# NRF51822.net
KiCad netlist of a schematic drawn in Altium Designer
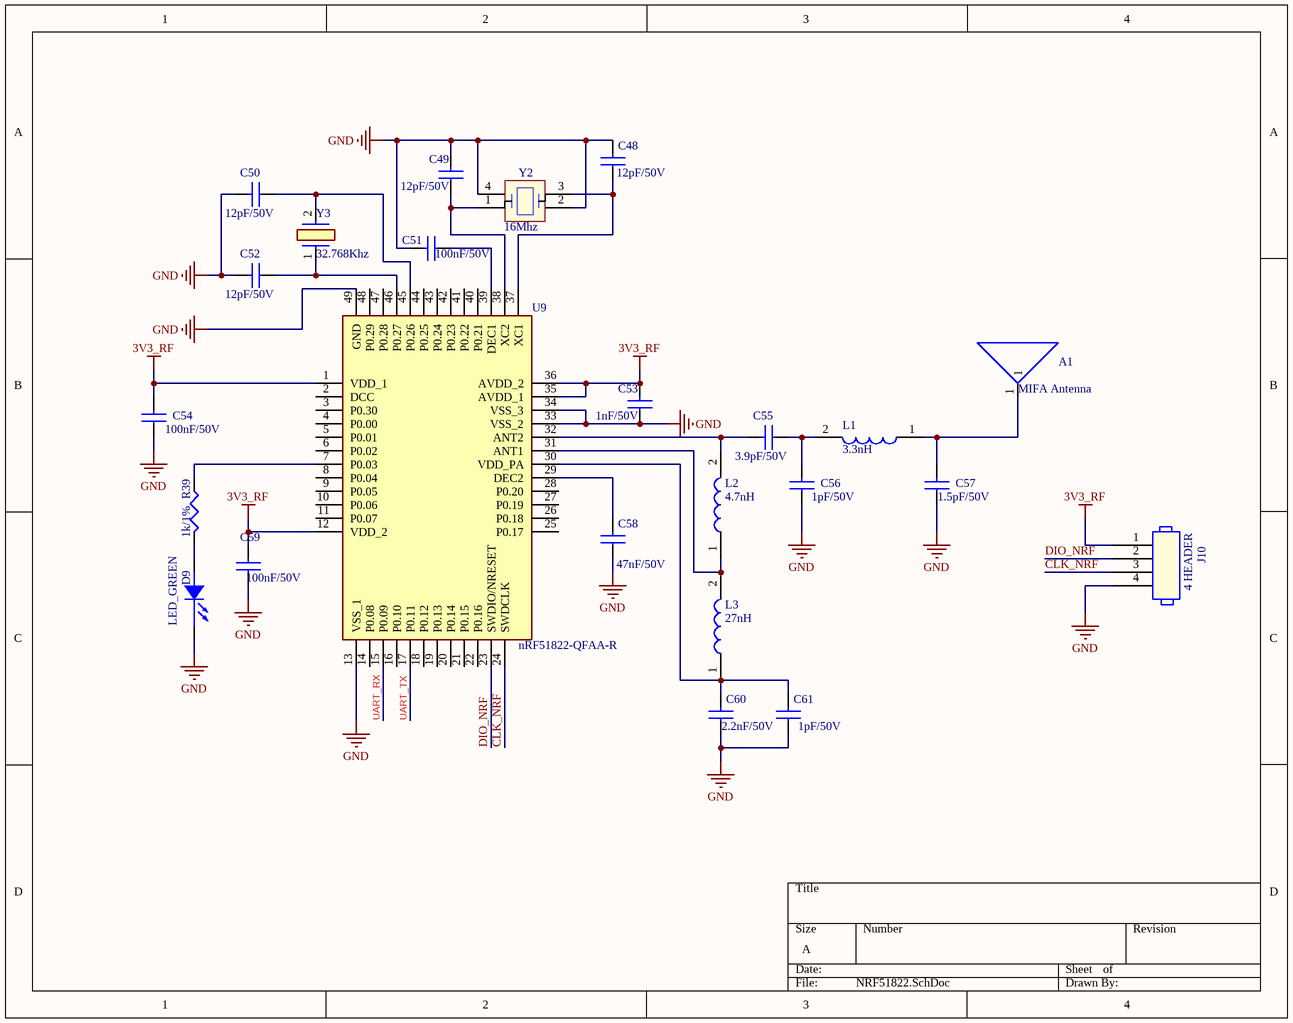
[diagram p0: NRF51822.SchDoc]

(export (version "E")
  (design (tool "Eeschema 10.0.6"))
  (components
    (comp (ref "A1")
      (value "MIFA Antenna")
      (footprint "ANT-2.4GHZ-8.0X1.0MM")
      (description "None")
      (libsource (lib "VESC_DEVICE_Library") (part "Ceramic _ANTENNA"))
    )
    (comp (ref "C48") (value "12pF/50V") (footprint "C0402") (libsource (lib "*") (part "CAP NP")))
    (comp (ref "C49") (value "12pF/50V") (footprint "C0402") (libsource (lib "*") (part "CAP NP")))
    (comp (ref "C50") (value "12pF/50V") (footprint "C0402") (libsource (lib "*") (part "CAP NP")))
    (comp (ref "C51") (value "100nF/50V") (footprint "C0402") (libsource (lib "*") (part "CAP NP")))
    (comp (ref "C52") (value "12pF/50V") (footprint "C0402") (libsource (lib "*") (part "CAP NP")))
    (comp (ref "C53") (value "1nF/50V") (footprint "C0402") (libsource (lib "*") (part "CAP NP")))
    (comp (ref "C54") (value "100nF/50V") (footprint "C0402") (libsource (lib "*") (part "CAP NP")))
    (comp (ref "C55") (value "3.9pF/50V") (footprint "C0402") (libsource (lib "*") (part "CAP NP")))
    (comp (ref "C56") (value "1pF/50V") (footprint "C0402") (libsource (lib "*") (part "CAP NP")))
    (comp (ref "C57") (value "1.5pF/50V") (footprint "C0402") (libsource (lib "*") (part "CAP NP")))
    (comp (ref "C58") (value "47nF/50V") (footprint "C0402") (libsource (lib "*") (part "CAP NP")))
    (comp (ref "C59") (value "100nF/50V") (footprint "C0402") (libsource (lib "*") (part "CAP NP")))
    (comp (ref "C60") (value "2.2nF/50V") (footprint "C0402") (libsource (lib "*") (part "CAP NP")))
    (comp (ref "C61") (value "1pF/50V") (footprint "C0402") (libsource (lib "*") (part "CAP NP")))
    (comp (ref "D9") (value "LED_GREEN") (footprint "LED0603") (libsource (lib "*") (part "LED")))
    (comp (ref "J10") (value "4 HEADER") (footprint "ISP-4P-2_54") (libsource (lib "*") (part "4 HEADER")))
    (comp (ref "L1")
      (value "3.3nH")
      (footprint "LQG15WH0N7B02D")
      (description "Inductor")
      (fields
        (field (name "MANUFACTURER_PART_NUMBER") "LQG15HS4N7C02D")
        (field (name "MOUSER PART NUMBER") "81-LQG15HS4N7C02D")
      )
      (libsource (lib "VESC_DEVICE_Library") (part "LQG15HS4N7C02D"))
    )
    (comp (ref "L2")
      (value "4.7nH")
      (footprint "LQG15WH0N7B02D")
      (description "Inductor")
      (fields
        (field (name "MANUFACTURER_PART_NUMBER") "LQG15HS4N7C02D")
        (field (name "MOUSER PART NUMBER") "81-LQG15HS4N7C02D")
      )
      (libsource (lib "VESC_DEVICE_Library") (part "LQG15HS4N7C02D"))
    )
    (comp (ref "L3")
      (value "27nH")
      (footprint "LQG15WH0N7B02D")
      (description "Inductor")
      (fields
        (field (name "MANUFACTURER_PART_NUMBER") "LQG15HS4N7C02D")
        (field (name "MOUSER PART NUMBER") "81-LQG15HS4N7C02D")
      )
      (libsource (lib "VESC_DEVICE_Library") (part "LQG15HS4N7C02D"))
    )
    (comp (ref "R39") (value "1k/1%") (footprint "R0402") (libsource (lib "*") (part "RESISTOR")))
    (comp (ref "U9")
      (value "nRF51822-QFAA-R")
      (footprint "SamacSys:QFN40P600X600X95-49N-D")
      (description "Integrated Circuit")
      (fields
        (field (name "MOUSER PART NUMBER") "949-NRF51822-QFAA-R")
        (field (name "ARROW PART NUMBER") "NRF51822-QFAA-R")
      )
      (libsource (lib "VESC_DEVICE_Library") (part "nRF51822-QFAA-R"))
    )
    (comp (ref "Y2")
      (value "16Mhz")
      (footprint "Q22FA12800400")
      (description "Crystal or Oscillator")
      (fields (field (name "MANUFACTURER_PART_NUMBER") "Q22FA12800400"))
      (libsource (lib "VESC_DEVICE_Library") (part "Q22FA12800400"))
    )
    (comp (ref "Y3")
      (value "32.768Khz")
      (footprint "ABS0532768KHZ9T")
      (description "Crystal or Oscillator")
      (fields
        (field (name "MANUFACTURER_PART_NUMBER") "ABS05-32.768KHZ-9-T")
        (field (name "MOUSER PART NUMBER") "815-ABS05-32.768K9T")
      )
      (libsource (lib "VESC_DEVICE_Library") (part "ABS05-32.768KHZ-9-T"))
    )
  )
  (nets
    (net (code "1") (name "/CLK_NRF") (class "Default")
      (node (ref "J10") (pin "3") (pinfunction "3_3") (pintype "passive"))
      (node (ref "U9") (pin "24") (pinfunction "SWDCLK_24") (pintype "passive"))
    )
    (net (code "2") (name "/DIO_NRF") (class "Default")
      (node (ref "J10") (pin "2") (pinfunction "2_2") (pintype "passive"))
      (node (ref "U9") (pin "23") (pinfunction "SWDIO/NRESET_23") (pintype "passive"))
    )
    (net (code "3") (name "/UART_RX") (class "Default")
      (node (ref "U9") (pin "15") (pinfunction "P0.09_15") (pintype "passive"))
    )
    (net (code "4") (name "/UART_TX") (class "Default")
      (node (ref "U9") (pin "17") (pinfunction "P0.11_17") (pintype "passive"))
    )
    (net (code "5") (name "3V3_RF") (class "Default")
      (node (ref "C53") (pin "2") (pinfunction "2_2") (pintype "passive"))
      (node (ref "C54") (pin "2") (pinfunction "2_2") (pintype "passive"))
      (node (ref "C59") (pin "2") (pinfunction "2_2") (pintype "passive"))
      (node (ref "J10") (pin "1") (pinfunction "1_1") (pintype "passive"))
      (node (ref "U9") (pin "1") (pinfunction "VDD_1_1") (pintype "passive"))
      (node (ref "U9") (pin "12") (pinfunction "VDD_2_12") (pintype "passive"))
      (node (ref "U9") (pin "35") (pinfunction "AVDD_1_35") (pintype "passive"))
      (node (ref "U9") (pin "36") (pinfunction "AVDD_2_36") (pintype "passive"))
    )
    (net (code "6") (name "GND") (class "Default")
      (node (ref "C48") (pin "2") (pinfunction "2_2") (pintype "passive"))
      (node (ref "C49") (pin "2") (pinfunction "2_2") (pintype "passive"))
      (node (ref "C50") (pin "2") (pinfunction "2_2") (pintype "passive"))
      (node (ref "C51") (pin "2") (pinfunction "2_2") (pintype "passive"))
      (node (ref "C52") (pin "2") (pinfunction "2_2") (pintype "passive"))
      (node (ref "C53") (pin "1") (pinfunction "1_1") (pintype "passive"))
      (node (ref "C54") (pin "1") (pinfunction "1_1") (pintype "passive"))
      (node (ref "C56") (pin "1") (pinfunction "1_1") (pintype "passive"))
      (node (ref "C57") (pin "1") (pinfunction "1_1") (pintype "passive"))
      (node (ref "C58") (pin "1") (pinfunction "1_1") (pintype "passive"))
      (node (ref "C59") (pin "1") (pinfunction "1_1") (pintype "passive"))
      (node (ref "C60") (pin "1") (pinfunction "1_1") (pintype "passive"))
      (node (ref "C61") (pin "1") (pinfunction "1_1") (pintype "passive"))
      (node (ref "D9") (pin "1") (pinfunction "CATHODE_1") (pintype "passive"))
      (node (ref "J10") (pin "4") (pinfunction "4_4") (pintype "passive"))
      (node (ref "U9") (pin "13") (pinfunction "VSS_1_13") (pintype "passive"))
      (node (ref "U9") (pin "33") (pinfunction "VSS_2_33") (pintype "passive"))
      (node (ref "U9") (pin "34") (pinfunction "VSS_3_34") (pintype "passive"))
      (node (ref "U9") (pin "49") (pinfunction "GND_49") (pintype "passive"))
      (node (ref "Y2") (pin "2") (pinfunction "GND_1_2") (pintype "passive"))
      (node (ref "Y2") (pin "4") (pinfunction "GND_2_4") (pintype "passive"))
    )
    (net (code "7") (name "Net-(A1-Pad1)") (class "Default")
      (node (ref "A1") (pin "1") (pinfunction "1_1") (pintype "passive"))
      (node (ref "C57") (pin "2") (pinfunction "2_2") (pintype "passive"))
      (node (ref "L1") (pin "1") (pinfunction "1_1") (pintype "passive"))
    )
    (net (code "8") (name "Net-(C55-Pad1)") (class "Default")
      (node (ref "C55") (pin "1") (pinfunction "1_1") (pintype "passive"))
      (node (ref "C56") (pin "2") (pinfunction "2_2") (pintype "passive"))
      (node (ref "L1") (pin "2") (pinfunction "2_2") (pintype "passive"))
    )
    (net (code "9") (name "Net-(D9-ANODE)") (class "Default")
      (node (ref "D9") (pin "2") (pinfunction "ANODE_2") (pintype "passive"))
      (node (ref "R39") (pin "1") (pinfunction "1_1") (pintype "passive"))
    )
    (net (code "10") (name "Net-(U9-ANT1)") (class "Default")
      (node (ref "L2") (pin "1") (pinfunction "1_1") (pintype "passive"))
      (node (ref "L3") (pin "2") (pinfunction "2_2") (pintype "passive"))
      (node (ref "U9") (pin "31") (pinfunction "ANT1_31") (pintype "passive"))
    )
    (net (code "11") (name "Net-(U9-ANT2)") (class "Default")
      (node (ref "C55") (pin "2") (pinfunction "2_2") (pintype "passive"))
      (node (ref "L2") (pin "2") (pinfunction "2_2") (pintype "passive"))
      (node (ref "U9") (pin "32") (pinfunction "ANT2_32") (pintype "passive"))
    )
    (net (code "12") (name "Net-(U9-DEC1)") (class "Default")
      (node (ref "C51") (pin "1") (pinfunction "1_1") (pintype "passive"))
      (node (ref "U9") (pin "39") (pinfunction "DEC1_39") (pintype "passive"))
    )
    (net (code "13") (name "Net-(U9-DEC2)") (class "Default")
      (node (ref "C58") (pin "2") (pinfunction "2_2") (pintype "passive"))
      (node (ref "U9") (pin "29") (pinfunction "DEC2_29") (pintype "passive"))
    )
    (net (code "14") (name "Net-(U9-P0.03)") (class "Default")
      (node (ref "R39") (pin "2") (pinfunction "2_2") (pintype "passive"))
      (node (ref "U9") (pin "7") (pinfunction "P0.03_7") (pintype "passive"))
    )
    (net (code "15") (name "Net-(U9-P0.26)") (class "Default")
      (node (ref "C50") (pin "1") (pinfunction "1_1") (pintype "passive"))
      (node (ref "U9") (pin "45") (pinfunction "P0.26_45") (pintype "passive"))
      (node (ref "Y3") (pin "2") (pinfunction "2_2") (pintype "passive"))
    )
    (net (code "16") (name "Net-(U9-P0.27)") (class "Default")
      (node (ref "C52") (pin "1") (pinfunction "1_1") (pintype "passive"))
      (node (ref "U9") (pin "46") (pinfunction "P0.27_46") (pintype "passive"))
      (node (ref "Y3") (pin "1") (pinfunction "1_1") (pintype "passive"))
    )
    (net (code "17") (name "Net-(U9-VDD_PA)") (class "Default")
      (node (ref "C60") (pin "2") (pinfunction "2_2") (pintype "passive"))
      (node (ref "C61") (pin "2") (pinfunction "2_2") (pintype "passive"))
      (node (ref "L3") (pin "1") (pinfunction "1_1") (pintype "passive"))
      (node (ref "U9") (pin "30") (pinfunction "VDD_PA_30") (pintype "passive"))
    )
    (net (code "18") (name "Net-(U9-XC1)") (class "Default")
      (node (ref "C48") (pin "1") (pinfunction "1_1") (pintype "passive"))
      (node (ref "U9") (pin "37") (pinfunction "XC1_37") (pintype "passive"))
      (node (ref "Y2") (pin "3") (pinfunction "CRYSTAL_2_3") (pintype "passive"))
    )
    (net (code "19") (name "Net-(U9-XC2)") (class "Default")
      (node (ref "C49") (pin "1") (pinfunction "1_1") (pintype "passive"))
      (node (ref "U9") (pin "38") (pinfunction "XC2_38") (pintype "passive"))
      (node (ref "Y2") (pin "1") (pinfunction "CRYSTAL_1_1") (pintype "passive"))
    )
    (net (code "20") (name "unconnected-(U9-DCC-Pad2)") (class "Default")
      (node (ref "U9") (pin "2") (pinfunction "DCC_2") (pintype "passive"))
    )
    (net (code "21") (name "unconnected-(U9-P0.00-Pad4)") (class "Default")
      (node (ref "U9") (pin "4") (pinfunction "P0.00_4") (pintype "passive"))
    )
    (net (code "22") (name "unconnected-(U9-P0.01-Pad5)") (class "Default")
      (node (ref "U9") (pin "5") (pinfunction "P0.01_5") (pintype "passive"))
    )
    (net (code "23") (name "unconnected-(U9-P0.02-Pad6)") (class "Default")
      (node (ref "U9") (pin "6") (pinfunction "P0.02_6") (pintype "passive"))
    )
    (net (code "24") (name "unconnected-(U9-P0.04-Pad8)") (class "Default")
      (node (ref "U9") (pin "8") (pinfunction "P0.04_8") (pintype "passive"))
    )
    (net (code "25") (name "unconnected-(U9-P0.05-Pad9)") (class "Default")
      (node (ref "U9") (pin "9") (pinfunction "P0.05_9") (pintype "passive"))
    )
    (net (code "26") (name "unconnected-(U9-P0.06-Pad10)") (class "Default")
      (node (ref "U9") (pin "10") (pinfunction "P0.06_10") (pintype "passive"))
    )
    (net (code "27") (name "unconnected-(U9-P0.07-Pad11)") (class "Default")
      (node (ref "U9") (pin "11") (pinfunction "P0.07_11") (pintype "passive"))
    )
    (net (code "28") (name "unconnected-(U9-P0.08-Pad14)") (class "Default")
      (node (ref "U9") (pin "14") (pinfunction "P0.08_14") (pintype "passive"))
    )
    (net (code "29") (name "unconnected-(U9-P0.10-Pad16)") (class "Default")
      (node (ref "U9") (pin "16") (pinfunction "P0.10_16") (pintype "passive"))
    )
    (net (code "30") (name "unconnected-(U9-P0.12-Pad18)") (class "Default")
      (node (ref "U9") (pin "18") (pinfunction "P0.12_18") (pintype "passive"))
    )
    (net (code "31") (name "unconnected-(U9-P0.13-Pad19)") (class "Default")
      (node (ref "U9") (pin "19") (pinfunction "P0.13_19") (pintype "passive"))
    )
    (net (code "32") (name "unconnected-(U9-P0.14-Pad20)") (class "Default")
      (node (ref "U9") (pin "20") (pinfunction "P0.14_20") (pintype "passive"))
    )
    (net (code "33") (name "unconnected-(U9-P0.15-Pad21)") (class "Default")
      (node (ref "U9") (pin "21") (pinfunction "P0.15_21") (pintype "passive"))
    )
    (net (code "34") (name "unconnected-(U9-P0.16-Pad22)") (class "Default")
      (node (ref "U9") (pin "22") (pinfunction "P0.16_22") (pintype "passive"))
    )
    (net (code "35") (name "unconnected-(U9-P0.17-Pad25)") (class "Default")
      (node (ref "U9") (pin "25") (pinfunction "P0.17_25") (pintype "passive"))
    )
    (net (code "36") (name "unconnected-(U9-P0.18-Pad26)") (class "Default")
      (node (ref "U9") (pin "26") (pinfunction "P0.18_26") (pintype "passive"))
    )
    (net (code "37") (name "unconnected-(U9-P0.19-Pad27)") (class "Default")
      (node (ref "U9") (pin "27") (pinfunction "P0.19_27") (pintype "passive"))
    )
    (net (code "38") (name "unconnected-(U9-P0.20-Pad28)") (class "Default")
      (node (ref "U9") (pin "28") (pinfunction "P0.20_28") (pintype "passive"))
    )
    (net (code "39") (name "unconnected-(U9-P0.21-Pad40)") (class "Default")
      (node (ref "U9") (pin "40") (pinfunction "P0.21_40") (pintype "passive"))
    )
    (net (code "40") (name "unconnected-(U9-P0.22-Pad41)") (class "Default")
      (node (ref "U9") (pin "41") (pinfunction "P0.22_41") (pintype "passive"))
    )
    (net (code "41") (name "unconnected-(U9-P0.23-Pad42)") (class "Default")
      (node (ref "U9") (pin "42") (pinfunction "P0.23_42") (pintype "passive"))
    )
    (net (code "42") (name "unconnected-(U9-P0.24-Pad43)") (class "Default")
      (node (ref "U9") (pin "43") (pinfunction "P0.24_43") (pintype "passive"))
    )
    (net (code "43") (name "unconnected-(U9-P0.25-Pad44)") (class "Default")
      (node (ref "U9") (pin "44") (pinfunction "P0.25_44") (pintype "passive"))
    )
    (net (code "44") (name "unconnected-(U9-P0.28-Pad47)") (class "Default")
      (node (ref "U9") (pin "47") (pinfunction "P0.28_47") (pintype "passive"))
    )
    (net (code "45") (name "unconnected-(U9-P0.29-Pad48)") (class "Default")
      (node (ref "U9") (pin "48") (pinfunction "P0.29_48") (pintype "passive"))
    )
    (net (code "46") (name "unconnected-(U9-P0.30-Pad3)") (class "Default")
      (node (ref "U9") (pin "3") (pinfunction "P0.30_3") (pintype "passive"))
    )
  )
)
